# 2-port_SPI-UART_bridge.net
KiCad netlist of a schematic drawn in Altium Designer
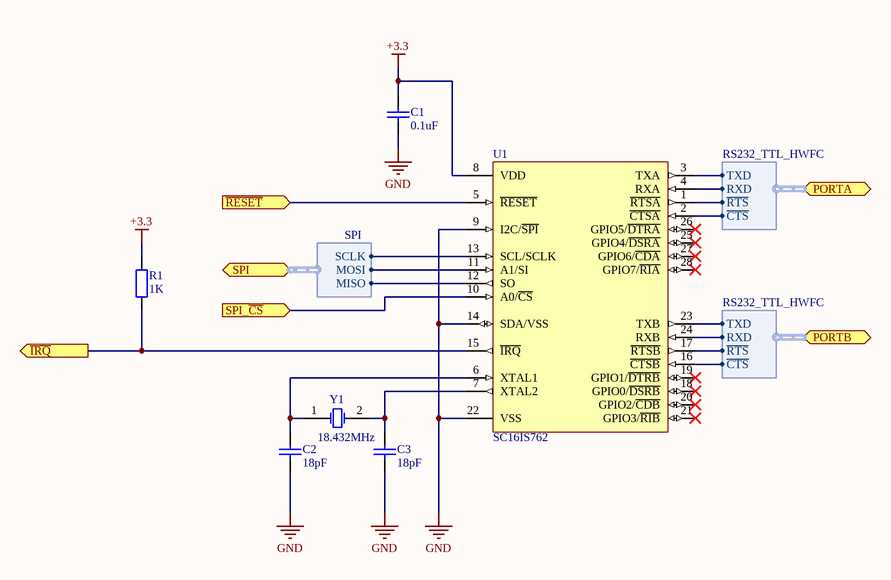
[diagram p0: 2-port SPI-UART bridge.SchDoc]

(export (version "E")
  (design (tool "Eeschema 10.0.6"))
  (components
    (comp (ref "C1")
      (value "0.1uF")
      (footprint "C0603")
      (description "Capacitor")
      (fields (field (name "Comment") "Cap"))
      (libsource (lib "Miscellaneous Devices") (part "Cap"))
    )
    (comp (ref "C2")
      (value "18pF")
      (footprint "C0603")
      (description "Capacitor")
      (fields (field (name "Comment") "Cap"))
      (libsource (lib "Miscellaneous Devices") (part "Cap"))
    )
    (comp (ref "C3")
      (value "18pF")
      (footprint "C0603")
      (description "Capacitor")
      (fields (field (name "Comment") "Cap"))
      (libsource (lib "Miscellaneous Devices") (part "Cap"))
    )
    (comp (ref "R1")
      (value "1K")
      (footprint "R0603")
      (description "Resistor")
      (fields (field (name "Comment") "Res"))
      (libsource (lib "Miscellaneous Devices") (part "Res2"))
    )
    (comp (ref "U1")
      (value "SC16IS762")
      (footprint "SC16IS762IPW")
      (description "NXP - SC16IS762IPW,112 - IC, DUAL UART, FIFO, 5MBPS 3.6V, TSSOP28")
      (libsource (lib "SC16IS762") (part "SC16IS762"))
    )
    (comp (ref "Y1")
      (value "18.432MHz")
      (footprint "7A-18.432MAAJ-T")
      (description "Crystal Oscillator")
      (fields (field (name "Comment") "XTAL") (field (name "PUBLISHER") "Altium Limited"))
      (libsource (lib "Miscellaneous Devices") (part "XTAL"))
    )
  )
  (nets
    (net (code "3") (name "+3.3") (class "Default")
      (node (ref "C1") (pin "1") (pinfunction "1_1") (pintype "passive"))
      (node (ref "R1") (pin "2") (pinfunction "2_2") (pintype "passive"))
      (node (ref "U1") (pin "8") (pinfunction "VDD_8") (pintype "power_in"))
    )
    (net (code "4") (name "/MISO") (class "Default")
      (node (ref "U1") (pin "12") (pinfunction "SO_12") (pintype "output"))
    )
    (net (code "5") (name "/MOSI") (class "Default")
      (node (ref "U1") (pin "11") (pinfunction "A1/SI_11") (pintype "input"))
    )
    (net (code "6") (name "/SCLK") (class "Default")
      (node (ref "U1") (pin "13") (pinfunction "SCL/SCLK_13") (pintype "input"))
    )
    (net (code "7") (name "/SPI_~{CS}") (class "Default")
      (node (ref "U1") (pin "10") (pinfunction "A0/~{CS}_10") (pintype "input"))
    )
    (net (code "10") (name "/~{IRQ}") (class "Default")
      (node (ref "R1") (pin "1") (pinfunction "1_1") (pintype "passive"))
      (node (ref "U1") (pin "15") (pinfunction "~{IRQ}_15") (pintype "output"))
    )
    (net (code "11") (name "/~{RESET}") (class "Default")
      (node (ref "U1") (pin "5") (pinfunction "~{RESET}_5") (pintype "input"))
    )
    (net (code "12") (name "GND") (class "Default")
      (node (ref "C1") (pin "2") (pinfunction "2_2") (pintype "passive"))
      (node (ref "C2") (pin "2") (pinfunction "2_2") (pintype "passive"))
      (node (ref "C3") (pin "2") (pinfunction "2_2") (pintype "passive"))
      (node (ref "U1") (pin "14") (pinfunction "SDA/VSS_14") (pintype "bidirectional"))
      (node (ref "U1") (pin "22") (pinfunction "VSS_22") (pintype "power_in"))
      (node (ref "U1") (pin "9") (pinfunction "I2C/~{SPI}_9") (pintype "input"))
    )
    (net (code "13") (name "Net-(U1-XTAL1)") (class "Default")
      (node (ref "C2") (pin "1") (pinfunction "1_1") (pintype "passive"))
      (node (ref "U1") (pin "6") (pinfunction "XTAL1_6") (pintype "input"))
      (node (ref "Y1") (pin "1") (pinfunction "OSC1_1") (pintype "passive"))
    )
    (net (code "14") (name "Net-(U1-XTAL2)") (class "Default")
      (node (ref "C3") (pin "1") (pinfunction "1_1") (pintype "passive"))
      (node (ref "U1") (pin "7") (pinfunction "XTAL2_7") (pintype "output"))
      (node (ref "Y1") (pin "2") (pinfunction "OSC2_2") (pintype "passive"))
    )
    (net (code "15") (name "unconnected-(U1-GPIO0{slash}~{DSRB}-Pad18)") (class "Default")
      (node (ref "U1") (pin "18") (pinfunction "GPIO0/~{DSRB}_18") (pintype "bidirectional+no_connect"))
    )
    (net (code "16") (name "unconnected-(U1-GPIO1{slash}~{DTRB}-Pad19)") (class "Default")
      (node (ref "U1") (pin "19") (pinfunction "GPIO1/~{DTRB}_19") (pintype "bidirectional+no_connect"))
    )
    (net (code "17") (name "unconnected-(U1-GPIO2{slash}~{CDB}-Pad20)") (class "Default")
      (node (ref "U1") (pin "20") (pinfunction "GPIO2/~{CDB}_20") (pintype "bidirectional+no_connect"))
    )
    (net (code "18") (name "unconnected-(U1-GPIO3{slash}~{RIB}-Pad21)") (class "Default")
      (node (ref "U1") (pin "21") (pinfunction "GPIO3/~{RIB}_21") (pintype "bidirectional+no_connect"))
    )
    (net (code "19") (name "unconnected-(U1-GPIO4{slash}~{DSRA}-Pad25)") (class "Default")
      (node (ref "U1") (pin "25") (pinfunction "GPIO4/~{DSRA}_25") (pintype "bidirectional+no_connect"))
    )
    (net (code "20") (name "unconnected-(U1-GPIO5{slash}~{DTRA}-Pad26)") (class "Default")
      (node (ref "U1") (pin "26") (pinfunction "GPIO5/~{DTRA}_26") (pintype "bidirectional+no_connect"))
    )
    (net (code "21") (name "unconnected-(U1-GPIO6{slash}~{CDA}-Pad27)") (class "Default")
      (node (ref "U1") (pin "27") (pinfunction "GPIO6/~{CDA}_27") (pintype "bidirectional+no_connect"))
    )
    (net (code "22") (name "unconnected-(U1-GPIO7{slash}~{RIA}-Pad28)") (class "Default")
      (node (ref "U1") (pin "28") (pinfunction "GPIO7/~{RIA}_28") (pintype "bidirectional+no_connect"))
    )
    (net (code "23") (name "unconnected-(U1-RXA-Pad4)") (class "Default")
      (node (ref "U1") (pin "4") (pinfunction "RXA_4") (pintype "input"))
    )
    (net (code "24") (name "unconnected-(U1-RXB-Pad24)") (class "Default")
      (node (ref "U1") (pin "24") (pinfunction "RXB_24") (pintype "input"))
    )
    (net (code "25") (name "unconnected-(U1-TXA-Pad3)") (class "Default")
      (node (ref "U1") (pin "3") (pinfunction "TXA_3") (pintype "output"))
    )
    (net (code "26") (name "unconnected-(U1-TXB-Pad23)") (class "Default")
      (node (ref "U1") (pin "23") (pinfunction "TXB_23") (pintype "output"))
    )
    (net (code "27") (name "unconnected-(U1-~{CTSA}-Pad2)") (class "Default")
      (node (ref "U1") (pin "2") (pinfunction "~{CTSA}_2") (pintype "input"))
    )
    (net (code "28") (name "unconnected-(U1-~{CTSB}-Pad16)") (class "Default")
      (node (ref "U1") (pin "16") (pinfunction "~{CTSB}_16") (pintype "input"))
    )
    (net (code "29") (name "unconnected-(U1-~{RTSA}-Pad1)") (class "Default")
      (node (ref "U1") (pin "1") (pinfunction "~{RTSA}_1") (pintype "output"))
    )
    (net (code "30") (name "unconnected-(U1-~{RTSB}-Pad17)") (class "Default")
      (node (ref "U1") (pin "17") (pinfunction "~{RTSB}_17") (pintype "output"))
    )
  )
)
